# untitled.net
KiCad netlist of a schematic drawn in EAGLE
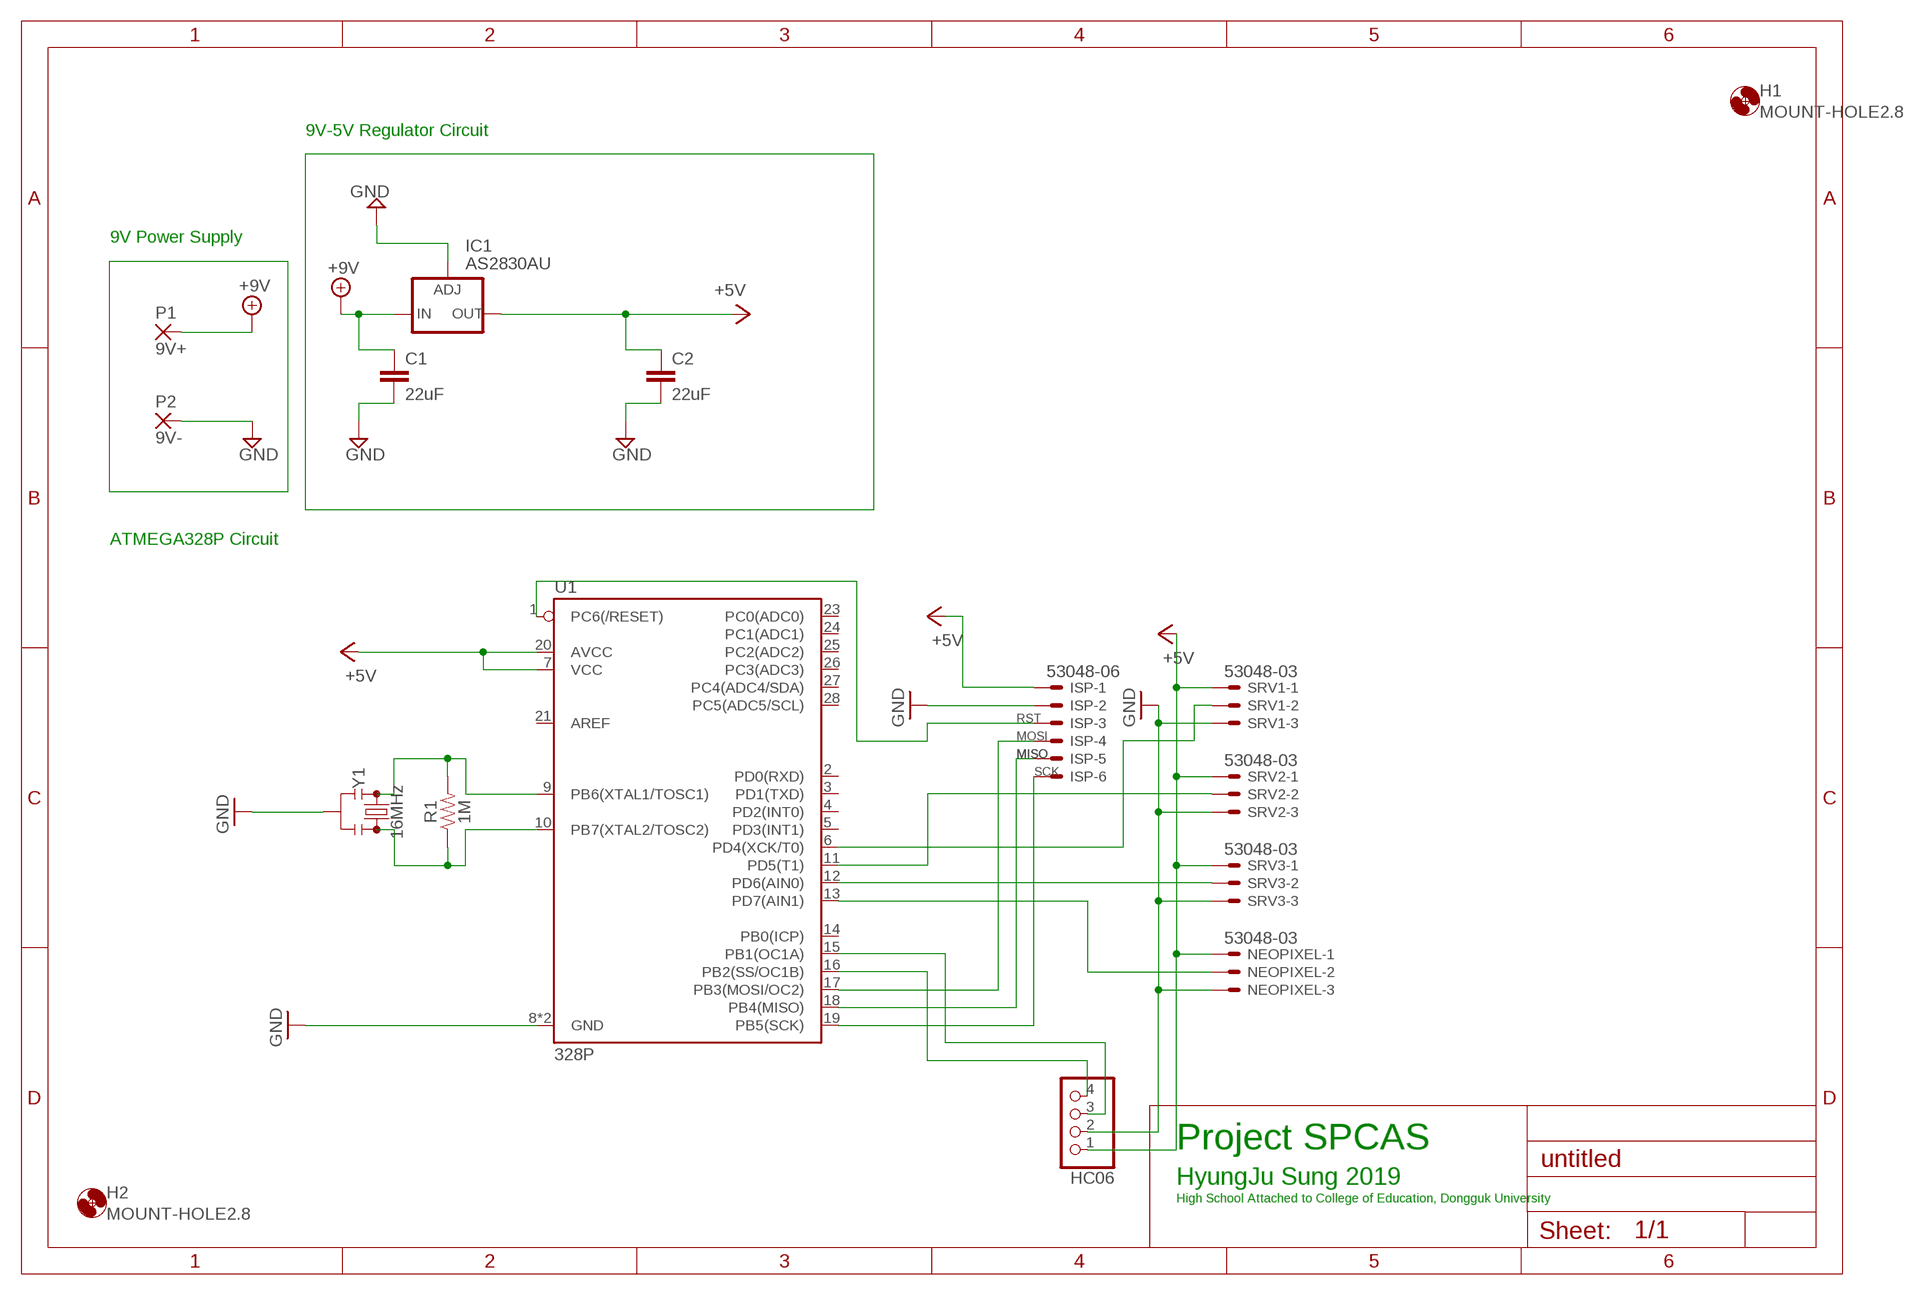
[diagram p0: schematic, sheet 1]

(export (version "E")
  (design (tool "Eeschema 10.0.6"))
  (components
    (comp (ref "C1")
      (value "22uF")
      (footprint "eagle-import:C2.5-2")
      (libsource (lib "eagle-import") (part "C2.5/2"))
    )
    (comp (ref "C2")
      (value "22uF")
      (footprint "eagle-import:C2.5-2")
      (libsource (lib "eagle-import") (part "C2.5/2"))
    )
    (comp (ref "H1")
      (value "MOUNT-HOLE2.8")
      (footprint "eagle-import:2,8")
      (libsource (lib "eagle-import") (part "MOUNT-HOLE2.8"))
    )
    (comp (ref "H2")
      (value "MOUNT-HOLE2.8")
      (footprint "eagle-import:2,8")
      (libsource (lib "eagle-import") (part "MOUNT-HOLE2.8"))
    )
    (comp (ref "HC06")
      (value "PINHD-1X4/90")
      (footprint "eagle-import:1X04_90")
      (libsource (lib "eagle-import") (part "PINHD-1X4/90"))
    )
    (comp (ref "IC1")
      (value "AS2830AU")
      (footprint "eagle-import:337TL")
      (libsource (lib "eagle-import") (part "LM337TL"))
    )
    (comp (ref "ISP")
      (value "53048-06")
      (footprint "eagle-import:53048-06")
      (fields (field (name "MF") "WALDOM/MOLEX") (field (name "MPN") "53048-0610"))
      (libsource (lib "eagle-import") (part "53?-06048"))
    )
    (comp (ref "NEOPIXEL")
      (value "53048-03")
      (footprint "eagle-import:53048-03")
      (fields (field (name "MF") "WALDOM/MOLEX") (field (name "MPN") "53048-0310"))
      (libsource (lib "eagle-import") (part "53?-03048"))
    )
    (comp (ref "P1")
      (value "9V+")
      (footprint "eagle-import:SMD2,54-5,08")
      (libsource (lib "eagle-import") (part "SMD5"))
    )
    (comp (ref "P2")
      (value "9V-")
      (footprint "eagle-import:SMD2,54-5,08")
      (libsource (lib "eagle-import") (part "SMD5"))
    )
    (comp (ref "R1")
      (value "1M")
      (footprint "eagle-import:AXIAL-0.3")
      (libsource (lib "eagle-import") (part "1MOHM-HORIZ-1/4W-5%"))
    )
    (comp (ref "SRV1")
      (value "53048-03")
      (footprint "eagle-import:53048-03")
      (fields (field (name "MF") "WALDOM/MOLEX") (field (name "MPN") "53048-0310"))
      (libsource (lib "eagle-import") (part "53?-03048"))
    )
    (comp (ref "SRV2")
      (value "53048-03")
      (footprint "eagle-import:53048-03")
      (fields (field (name "MF") "WALDOM/MOLEX") (field (name "MPN") "53048-0310"))
      (libsource (lib "eagle-import") (part "53?-03048"))
    )
    (comp (ref "SRV3")
      (value "53048-03")
      (footprint "eagle-import:53048-03")
      (fields (field (name "MF") "WALDOM/MOLEX") (field (name "MPN") "53048-0310"))
      (libsource (lib "eagle-import") (part "53?-03048"))
    )
    (comp (ref "U1")
      (value "328P")
      (footprint "eagle-import:DIP28")
      (libsource (lib "eagle-import") (part "ATMEGA328P_PDIP"))
    )
    (comp (ref "Y1")
      (value "16MHz")
      (footprint "eagle-import:RESONATOR-SMD-3.2X1.3")
      (libsource (lib "eagle-import") (part "RESONATOR-16MHZSMD_3.2X1.3"))
    )
  )
  (nets
    (net (code "1") (name "+5V") (class "Default")
      (node (ref "C2") (pin "1") (pinfunction "1_1") (pintype "passive"))
      (node (ref "HC06") (pin "1") (pinfunction "1_1") (pintype "passive"))
      (node (ref "IC1") (pin "3") (pinfunction "OUT_3") (pintype "passive"))
      (node (ref "ISP") (pin "1") (pinfunction "S_1") (pintype "passive"))
      (node (ref "NEOPIXEL") (pin "1") (pinfunction "S_1") (pintype "passive"))
      (node (ref "SRV1") (pin "1") (pinfunction "S_1") (pintype "passive"))
      (node (ref "SRV2") (pin "1") (pinfunction "S_1") (pintype "passive"))
      (node (ref "SRV3") (pin "1") (pinfunction "S_1") (pintype "passive"))
      (node (ref "U1") (pin "20") (pinfunction "AVCC_20") (pintype "bidirectional"))
      (node (ref "U1") (pin "7") (pinfunction "VCC_7") (pintype "bidirectional"))
    )
    (net (code "2") (name "+9V") (class "Default")
      (node (ref "C1") (pin "1") (pinfunction "1_1") (pintype "passive"))
      (node (ref "IC1") (pin "2") (pinfunction "IN_2") (pintype "input"))
      (node (ref "P1") (pin "1") (pinfunction "P_1") (pintype "passive"))
    )
    (net (code "3") (name "/MISO") (class "Default")
      (node (ref "ISP") (pin "5") (pinfunction "S_5") (pintype "passive"))
      (node (ref "U1") (pin "18") (pinfunction "PB4(MISO)_18") (pintype "bidirectional"))
    )
    (net (code "4") (name "/MOSI") (class "Default")
      (node (ref "ISP") (pin "4") (pinfunction "S_4") (pintype "passive"))
      (node (ref "U1") (pin "17") (pinfunction "PB3(MOSI/OC2)_17") (pintype "bidirectional"))
    )
    (net (code "5") (name "/RST") (class "Default")
      (node (ref "ISP") (pin "3") (pinfunction "S_3") (pintype "passive"))
      (node (ref "U1") (pin "1") (pinfunction "PC6(/RESET)_1") (pintype "bidirectional"))
    )
    (net (code "6") (name "/SCK") (class "Default")
      (node (ref "ISP") (pin "6") (pinfunction "S_6") (pintype "passive"))
      (node (ref "U1") (pin "19") (pinfunction "PB5(SCK)_19") (pintype "bidirectional"))
    )
    (net (code "7") (name "GND") (class "Default")
      (node (ref "C1") (pin "2") (pinfunction "2_2") (pintype "passive"))
      (node (ref "C2") (pin "2") (pinfunction "2_2") (pintype "passive"))
      (node (ref "HC06") (pin "2") (pinfunction "2_2") (pintype "passive"))
      (node (ref "IC1") (pin "1") (pinfunction "ADJ_1") (pintype "input"))
      (node (ref "ISP") (pin "2") (pinfunction "S_2") (pintype "passive"))
      (node (ref "NEOPIXEL") (pin "3") (pinfunction "S_3") (pintype "passive"))
      (node (ref "P2") (pin "1") (pinfunction "P_1") (pintype "passive"))
      (node (ref "SRV1") (pin "3") (pinfunction "S_3") (pintype "passive"))
      (node (ref "SRV2") (pin "3") (pinfunction "S_3") (pintype "passive"))
      (node (ref "SRV3") (pin "3") (pinfunction "S_3") (pintype "passive"))
      (node (ref "U1") (pin "22") (pinfunction "GND_22") (pintype "bidirectional"))
      (node (ref "U1") (pin "8") (pinfunction "GND_8") (pintype "bidirectional"))
      (node (ref "Y1") (pin "2") (pinfunction "2_2") (pintype "passive"))
    )
    (net (code "8") (name "Net-(NEOPIXELB-S)") (class "Default")
      (node (ref "NEOPIXEL") (pin "2") (pinfunction "S_2") (pintype "passive"))
      (node (ref "U1") (pin "13") (pinfunction "PD7(AIN1)_13") (pintype "bidirectional"))
    )
    (net (code "9") (name "Net-(R1-1)") (class "Default")
      (node (ref "R1") (pin "P$1") (pinfunction "1_P$1") (pintype "passive"))
      (node (ref "U1") (pin "10") (pinfunction "PB7(XTAL2/TOSC2)_10") (pintype "bidirectional"))
      (node (ref "Y1") (pin "3") (pinfunction "3_3") (pintype "passive"))
    )
    (net (code "10") (name "Net-(R1-2)") (class "Default")
      (node (ref "R1") (pin "P$2") (pinfunction "2_P$2") (pintype "passive"))
      (node (ref "U1") (pin "9") (pinfunction "PB6(XTAL1/TOSC1)_9") (pintype "bidirectional"))
      (node (ref "Y1") (pin "1") (pinfunction "1_1") (pintype "passive"))
    )
    (net (code "11") (name "Net-(SRV1B-S)") (class "Default")
      (node (ref "SRV1") (pin "2") (pinfunction "S_2") (pintype "passive"))
      (node (ref "U1") (pin "6") (pinfunction "PD4(XCK/T0)_6") (pintype "bidirectional"))
    )
    (net (code "12") (name "Net-(SRV2B-S)") (class "Default")
      (node (ref "SRV2") (pin "2") (pinfunction "S_2") (pintype "passive"))
      (node (ref "U1") (pin "11") (pinfunction "PD5(T1)_11") (pintype "bidirectional"))
    )
    (net (code "13") (name "Net-(SRV3B-S)") (class "Default")
      (node (ref "SRV3") (pin "2") (pinfunction "S_2") (pintype "passive"))
      (node (ref "U1") (pin "12") (pinfunction "PD6(AIN0)_12") (pintype "bidirectional"))
    )
    (net (code "14") (name "Net-(U1-PB1(OC1A))") (class "Default")
      (node (ref "HC06") (pin "3") (pinfunction "3_3") (pintype "passive"))
      (node (ref "U1") (pin "15") (pinfunction "PB1(OC1A)_15") (pintype "bidirectional"))
    )
    (net (code "15") (name "Net-(U1-PB2(SS{slash}OC1B))") (class "Default")
      (node (ref "HC06") (pin "4") (pinfunction "4_4") (pintype "passive"))
      (node (ref "U1") (pin "16") (pinfunction "PB2(SS/OC1B)_16") (pintype "bidirectional"))
    )
    (net (code "16") (name "unconnected-(U1-AREF-Pad21)") (class "Default")
      (node (ref "U1") (pin "21") (pinfunction "AREF_21") (pintype "bidirectional"))
    )
    (net (code "17") (name "unconnected-(U1-PB0(ICP)-Pad14)") (class "Default")
      (node (ref "U1") (pin "14") (pinfunction "PB0(ICP)_14") (pintype "bidirectional"))
    )
    (net (code "18") (name "unconnected-(U1-PC0(ADC0)-Pad23)") (class "Default")
      (node (ref "U1") (pin "23") (pinfunction "PC0(ADC0)_23") (pintype "bidirectional"))
    )
    (net (code "19") (name "unconnected-(U1-PC1(ADC1)-Pad24)") (class "Default")
      (node (ref "U1") (pin "24") (pinfunction "PC1(ADC1)_24") (pintype "bidirectional"))
    )
    (net (code "20") (name "unconnected-(U1-PC2(ADC2)-Pad25)") (class "Default")
      (node (ref "U1") (pin "25") (pinfunction "PC2(ADC2)_25") (pintype "bidirectional"))
    )
    (net (code "21") (name "unconnected-(U1-PC3(ADC3)-Pad26)") (class "Default")
      (node (ref "U1") (pin "26") (pinfunction "PC3(ADC3)_26") (pintype "bidirectional"))
    )
    (net (code "22") (name "unconnected-(U1-PC4(ADC4{slash}SDA)-Pad27)") (class "Default")
      (node (ref "U1") (pin "27") (pinfunction "PC4(ADC4/SDA)_27") (pintype "bidirectional"))
    )
    (net (code "23") (name "unconnected-(U1-PC5(ADC5{slash}SCL)-Pad28)") (class "Default")
      (node (ref "U1") (pin "28") (pinfunction "PC5(ADC5/SCL)_28") (pintype "bidirectional"))
    )
    (net (code "24") (name "unconnected-(U1-PD0(RXD)-Pad2)") (class "Default")
      (node (ref "U1") (pin "2") (pinfunction "PD0(RXD)_2") (pintype "bidirectional"))
    )
    (net (code "25") (name "unconnected-(U1-PD1(TXD)-Pad3)") (class "Default")
      (node (ref "U1") (pin "3") (pinfunction "PD1(TXD)_3") (pintype "bidirectional"))
    )
    (net (code "26") (name "unconnected-(U1-PD2(INT0)-Pad4)") (class "Default")
      (node (ref "U1") (pin "4") (pinfunction "PD2(INT0)_4") (pintype "bidirectional"))
    )
    (net (code "27") (name "unconnected-(U1-PD3(INT1)-Pad5)") (class "Default")
      (node (ref "U1") (pin "5") (pinfunction "PD3(INT1)_5") (pintype "bidirectional"))
    )
  )
)
